# Ideal_Diode.net
KiCad netlist of a schematic drawn in EAGLE
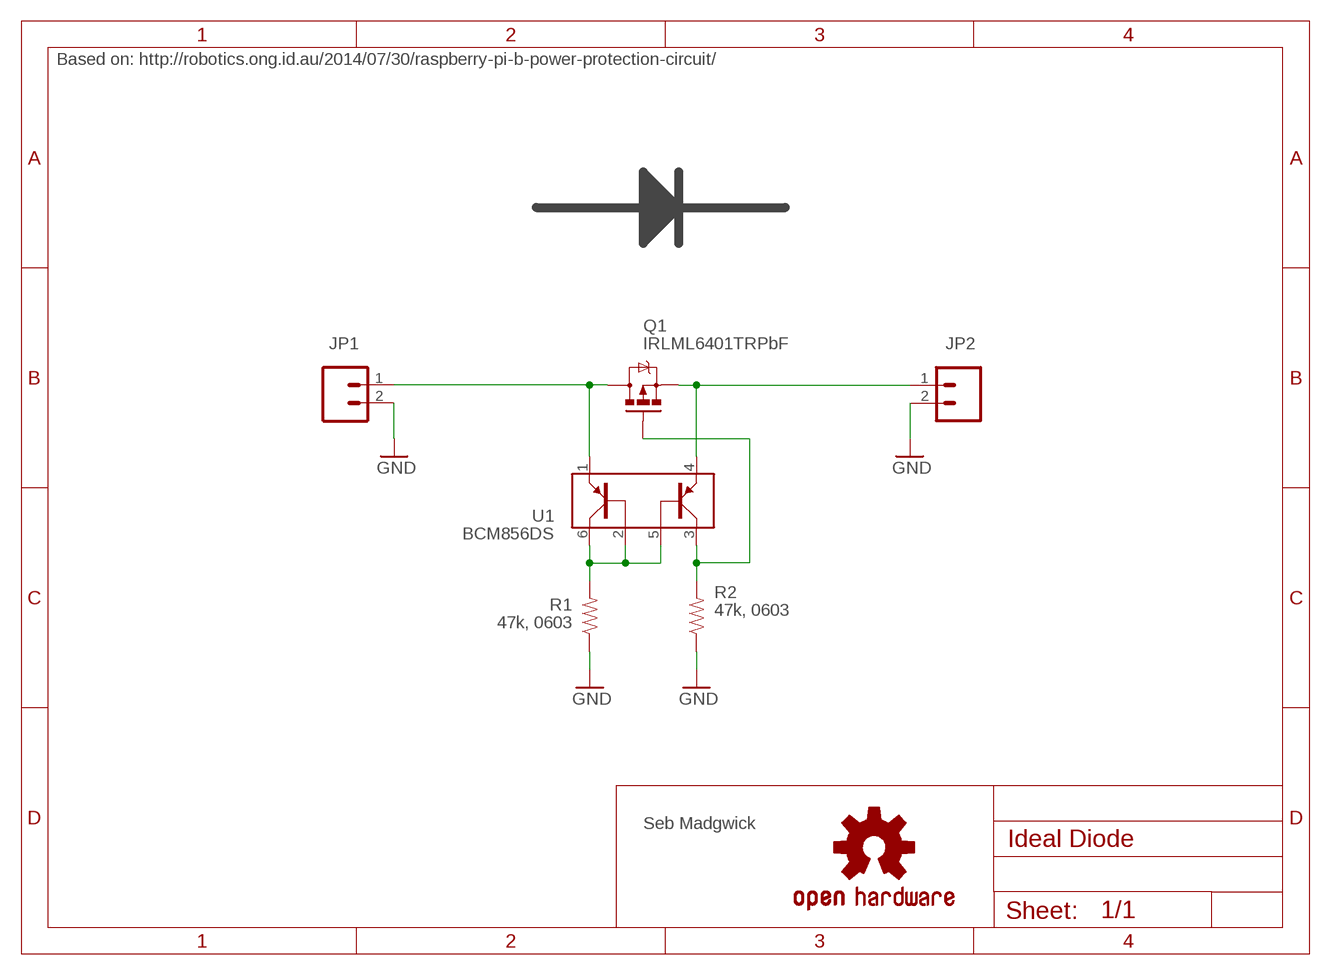
[diagram p0: schematic, sheet 1]

(export (version "E")
  (design (tool "Eeschema 10.0.6"))
  (components
    (comp (ref "JP1")
      (value "M02PTH3")
      (footprint "eagle-import:1X02_LONGPADS")
      (libsource (lib "eagle-import") (part "M02PTH3"))
    )
    (comp (ref "JP2")
      (value "M02PTH3")
      (footprint "eagle-import:1X02_LONGPADS")
      (libsource (lib "eagle-import") (part "M02PTH3"))
    )
    (comp (ref "LOGO1")
      (value "OSHW-LOGOS")
      (footprint "eagle-import:OSHW-LOGO-S")
      (libsource (lib "eagle-import") (part "OSHW-LOGOS"))
    )
    (comp (ref "Q1")
      (value "IRLML6401TRPbF")
      (footprint "eagle-import:SOT23-3")
      (libsource (lib "eagle-import") (part "MOSFET-PCHANNEL"))
    )
    (comp (ref "R1")
      (value "47k, 0603")
      (footprint "eagle-import:0603-RES")
      (libsource (lib "eagle-import") (part "RESISTOR0603"))
    )
    (comp (ref "R2")
      (value "47k, 0603")
      (footprint "eagle-import:0603-RES")
      (libsource (lib "eagle-import") (part "RESISTOR0603"))
    )
    (comp (ref "U1")
      (value "BCM856DS")
      (footprint "eagle-import:SOT457")
      (libsource (lib "eagle-import") (part "BCM856-MIRRORDS"))
    )
  )
  (nets
    (net (code "1") (name "GND") (class "Default")
      (node (ref "JP1") (pin "2") (pinfunction "2_2") (pintype "passive"))
      (node (ref "JP2") (pin "2") (pinfunction "2_2") (pintype "passive"))
      (node (ref "R1") (pin "1") (pinfunction "1_1") (pintype "passive"))
      (node (ref "R2") (pin "1") (pinfunction "1_1") (pintype "passive"))
    )
    (net (code "2") (name "Net-(Q1-D)") (class "Default")
      (node (ref "JP1") (pin "1") (pinfunction "1_1") (pintype "passive"))
      (node (ref "Q1") (pin "3") (pinfunction "D_3") (pintype "passive"))
      (node (ref "U1") (pin "1") (pintype "bidirectional"))
    )
    (net (code "3") (name "Net-(Q1-G)") (class "Default")
      (node (ref "Q1") (pin "1") (pinfunction "G_1") (pintype "passive"))
      (node (ref "R2") (pin "2") (pinfunction "2_2") (pintype "passive"))
      (node (ref "U1") (pin "3") (pintype "bidirectional"))
    )
    (net (code "4") (name "Net-(Q1-S)") (class "Default")
      (node (ref "JP2") (pin "1") (pinfunction "1_1") (pintype "passive"))
      (node (ref "Q1") (pin "2") (pinfunction "S_2") (pintype "passive"))
      (node (ref "U1") (pin "4") (pintype "bidirectional"))
    )
    (net (code "5") (name "Net-(R1-Pad2)") (class "Default")
      (node (ref "R1") (pin "2") (pinfunction "2_2") (pintype "passive"))
      (node (ref "U1") (pin "2") (pintype "bidirectional"))
      (node (ref "U1") (pin "5") (pintype "bidirectional"))
      (node (ref "U1") (pin "6") (pintype "bidirectional"))
    )
  )
)
